# RTS_Hub_V1_2.net
KiCad netlist of a schematic drawn in EAGLE
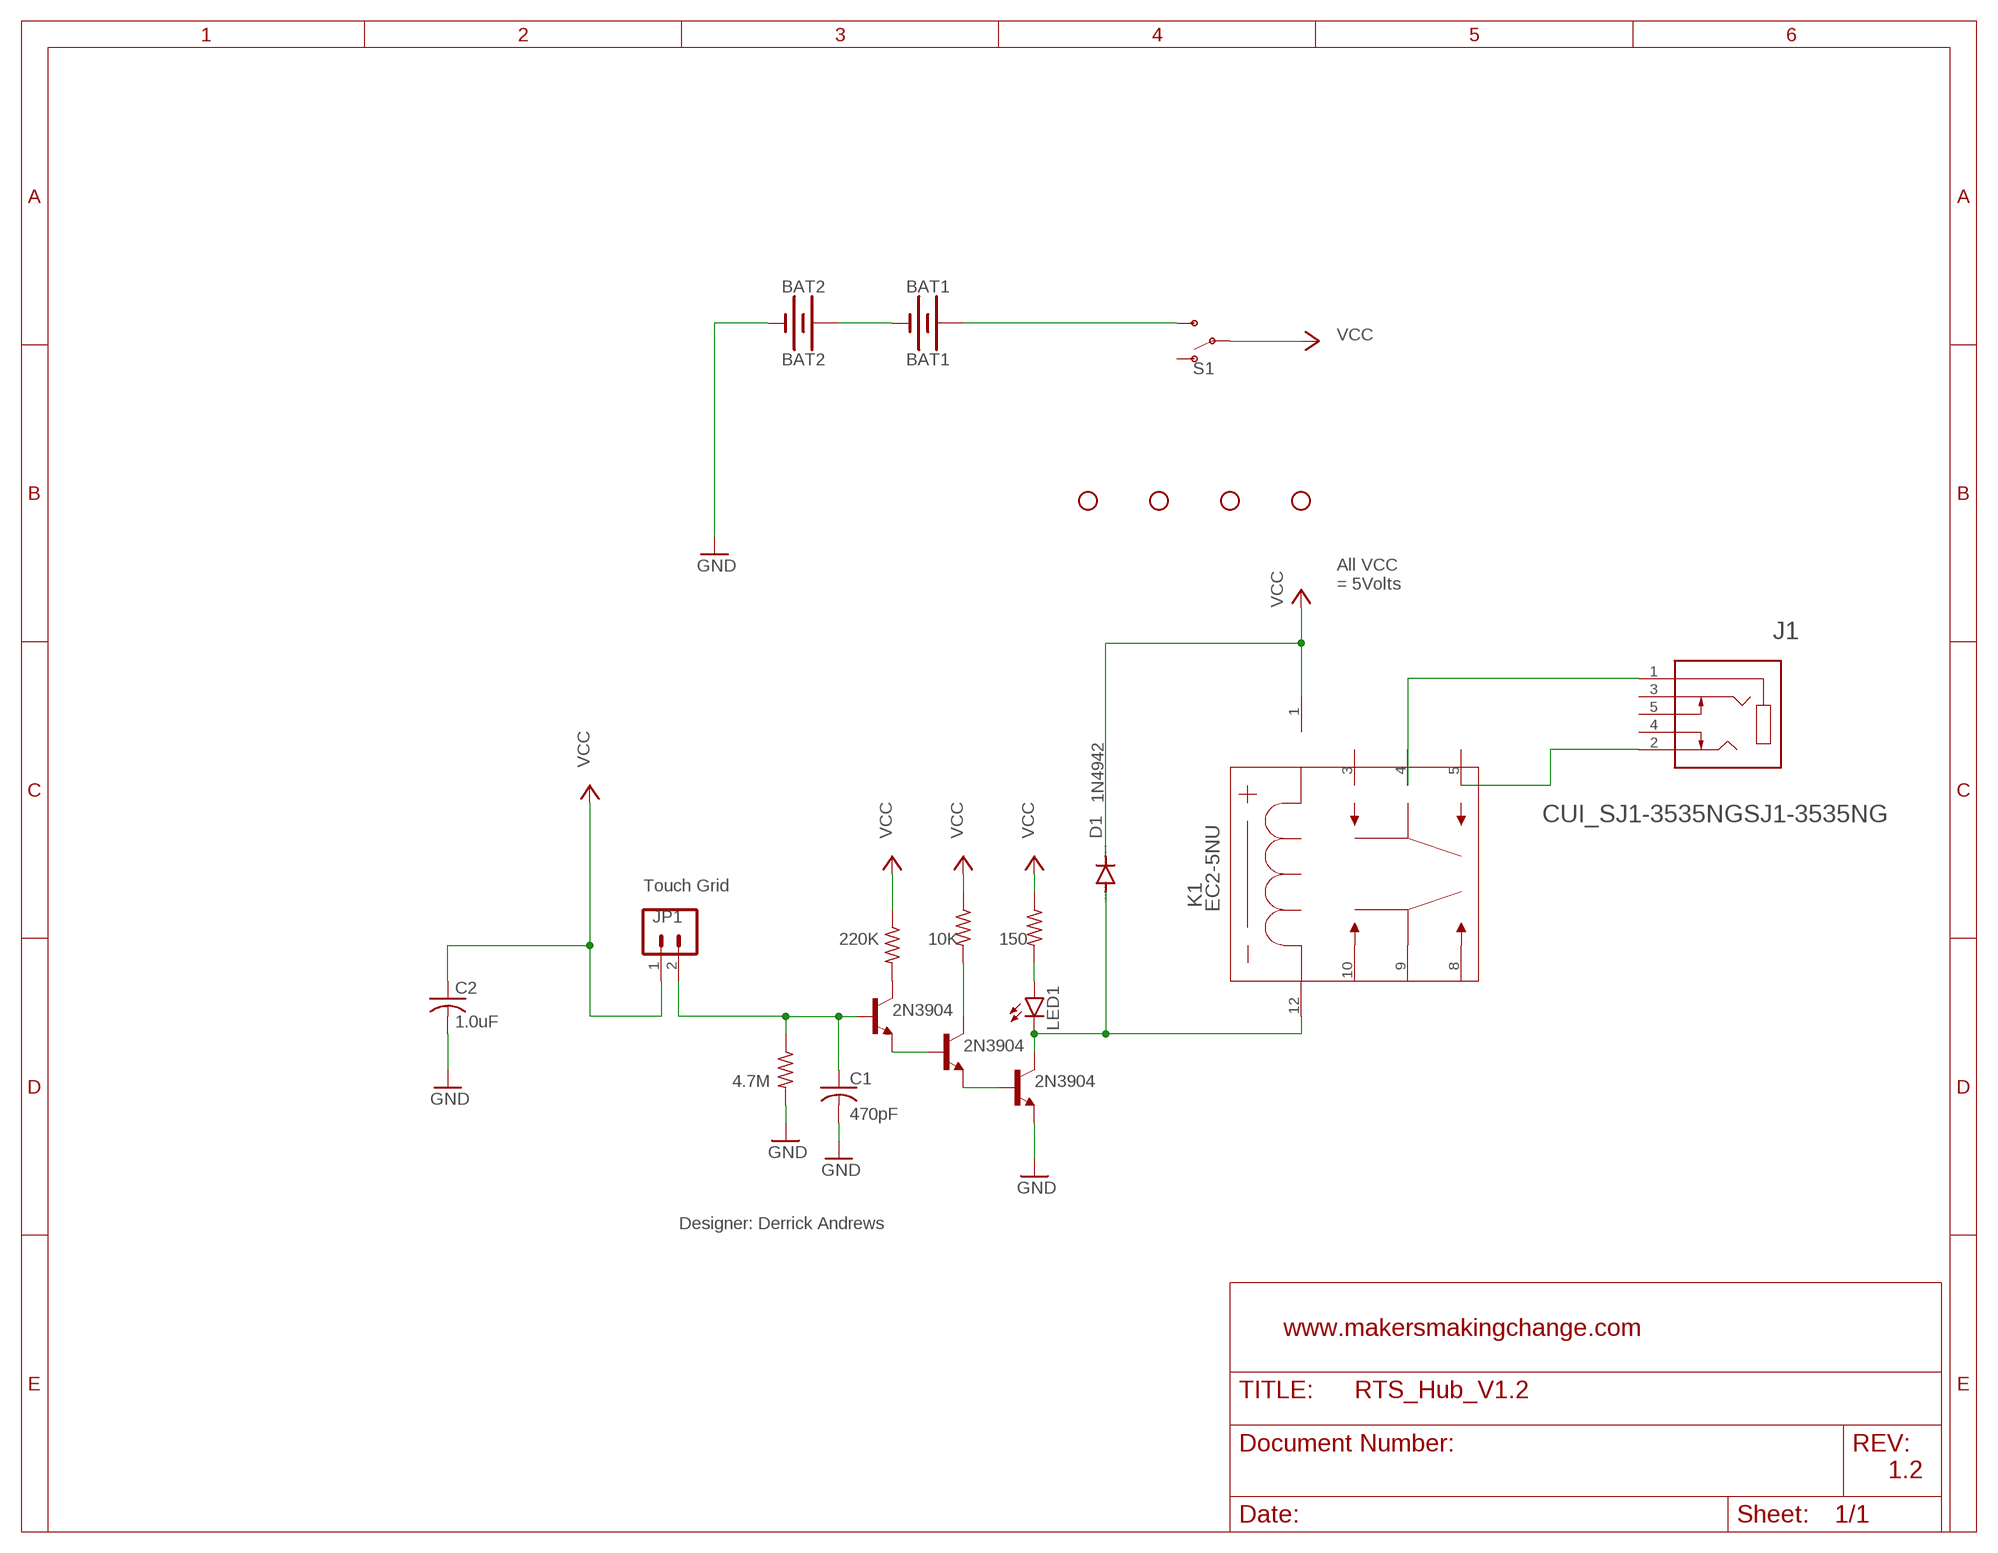
[diagram p0: schematic, sheet 1]

(export (version "E")
  (design (tool "Eeschema 10.0.6"))
  (components
    (comp (ref "BAT1")
      (value "BAT1")
      (footprint "eagle-import:BATTCOM_20MM_PTH")
      (libsource (lib "eagle-import") (part "BATTERY-20MM_PTH"))
    )
    (comp (ref "BAT2")
      (value "BAT2")
      (footprint "eagle-import:BATTCOM_20MM_PTH")
      (libsource (lib "eagle-import") (part "BATTERY-20MM_PTH"))
    )
    (comp (ref "C1")
      (value "470pF")
      (footprint "eagle-import:C025-030X050")
      (libsource (lib "eagle-import") (part "CAPACITOR-US-025"))
    )
    (comp (ref "C2")
      (value "1.0uF")
      (footprint "eagle-import:C050-030X075")
      (libsource (lib "eagle-import") (part "CAPACITOR-US-050"))
    )
    (comp (ref "D1")
      (value "1N4942")
      (footprint "eagle-import:DO41-10")
      (libsource (lib "eagle-import") (part "DIODE-DO41"))
    )
    (comp (ref "H1")
      (value "STAND-OFF-")
      (footprint "eagle-import:STAND-OFF")
      (libsource (lib "eagle-import") (part "STAND-OFF-"))
    )
    (comp (ref "H2")
      (value "STAND-OFF-")
      (footprint "eagle-import:STAND-OFF")
      (libsource (lib "eagle-import") (part "STAND-OFF-"))
    )
    (comp (ref "H3")
      (value "STAND-OFF-")
      (footprint "eagle-import:STAND-OFF")
      (libsource (lib "eagle-import") (part "STAND-OFF-"))
    )
    (comp (ref "H4")
      (value "STAND-OFF-")
      (footprint "eagle-import:STAND-OFF")
      (libsource (lib "eagle-import") (part "STAND-OFF-"))
    )
    (comp (ref "J1")
      (value "CUI_SJ1-3535NGSJ1-3535NG")
      (footprint "eagle-import:CUI_SJ1-3535NG")
      (libsource (lib "eagle-import") (part "CUI_SJ1-3535NGSJ1-3535NG"))
    )
    (comp (ref "JP1")
      (value "HEADER_1X02-1X02")
      (footprint "eagle-import:1X02")
      (libsource (lib "eagle-import") (part "HEADER_1X02-1X02"))
    )
    (comp (ref "K1")
      (value "EC2-5NU")
      (footprint "eagle-import:EC2NU")
      (fields (field (name "MANUFACTURER_PART_NUMBER") "EC25NU"))
      (libsource (lib "eagle-import") (part "EC2-5NU"))
    )
    (comp (ref "LED1")
      (value "LED5MM")
      (footprint "eagle-import:LED_5MM")
      (libsource (lib "eagle-import") (part "LED5MM"))
    )
    (comp (ref "R1")
      (value "10K")
      (footprint "eagle-import:RESISTOR_0207_7")
      (libsource (lib "eagle-import") (part "RESISTOR-US-0207/7"))
    )
    (comp (ref "R2")
      (value "4.7M")
      (footprint "eagle-import:RESISTOR_0207_7")
      (libsource (lib "eagle-import") (part "RESISTOR-US-0207/7"))
    )
    (comp (ref "R3")
      (value "220K")
      (footprint "eagle-import:RESISTOR_0207_7")
      (libsource (lib "eagle-import") (part "RESISTOR-US-0207/7"))
    )
    (comp (ref "R4")
      (value "150")
      (footprint "eagle-import:RESISTOR_0207_7")
      (libsource (lib "eagle-import") (part "RESISTOR-US-0207/7"))
    )
    (comp (ref "S1")
      (value "SWITCH-SPDT-PTH_11.6X4.0MM")
      (footprint "eagle-import:SWITCH_SPDT_PTH_11.6X4.0MM")
      (libsource (lib "eagle-import") (part "SWITCH-SPDT-PTH_11.6X4.0MM"))
    )
    (comp (ref "T1")
      (value "2N3904")
      (footprint "eagle-import:TO92-CBE")
      (libsource (lib "eagle-import") (part "2N3904"))
    )
    (comp (ref "T2")
      (value "2N3904")
      (footprint "eagle-import:TO92-CBE")
      (libsource (lib "eagle-import") (part "2N3904"))
    )
    (comp (ref "T3")
      (value "2N3904")
      (footprint "eagle-import:TO92-CBE")
      (libsource (lib "eagle-import") (part "2N3904"))
    )
  )
  (nets
    (net (code "1") (name "GND") (class "Default")
      (node (ref "BAT2") (pin "-") (pinfunction "-_-") (pintype "power_in"))
      (node (ref "C1") (pin "2") (pinfunction "2_2") (pintype "passive"))
      (node (ref "C2") (pin "2") (pinfunction "2_2") (pintype "passive"))
      (node (ref "R2") (pin "2") (pinfunction "2_2") (pintype "passive"))
      (node (ref "T1") (pin "E") (pinfunction "E_E") (pintype "passive"))
    )
    (net (code "2") (name "Net-(BAT1-Pad-)") (class "Default")
      (node (ref "BAT1") (pin "-") (pinfunction "-_-") (pintype "power_in"))
      (node (ref "BAT2") (pin "+") (pinfunction "+_+") (pintype "power_in"))
    )
    (net (code "3") (name "Net-(C1-Pad1)") (class "Default")
      (node (ref "C1") (pin "1") (pinfunction "1_1") (pintype "passive"))
      (node (ref "JP1") (pin "2") (pinfunction "2_2") (pintype "passive"))
      (node (ref "R2") (pin "1") (pinfunction "1_1") (pintype "passive"))
      (node (ref "T3") (pin "B") (pinfunction "B_B") (pintype "passive"))
    )
    (net (code "4") (name "Net-(K1-3)") (class "Default")
      (node (ref "J1") (pin "1") (pinfunction "1_1") (pintype "passive"))
      (node (ref "K1") (pin "4") (pinfunction "3_4") (pintype "passive"))
    )
    (net (code "5") (name "Net-(K1-4)") (class "Default")
      (node (ref "J1") (pin "2") (pinfunction "2_2") (pintype "passive"))
      (node (ref "K1") (pin "5") (pinfunction "4_5") (pintype "passive"))
    )
    (net (code "6") (name "Net-(K1-8)") (class "Default")
      (node (ref "D1") (pin "A") (pinfunction "A_A") (pintype "passive"))
      (node (ref "K1") (pin "12") (pinfunction "8_12") (pintype "passive"))
      (node (ref "LED1") (pin "K") (pinfunction "C_K") (pintype "passive"))
      (node (ref "T1") (pin "C") (pinfunction "C_C") (pintype "passive"))
    )
    (net (code "7") (name "Net-(LED1-PadA)") (class "Default")
      (node (ref "LED1") (pin "A") (pinfunction "A_A") (pintype "passive"))
      (node (ref "R4") (pin "2") (pinfunction "2_2") (pintype "passive"))
    )
    (net (code "8") (name "Net-(R1-Pad2)") (class "Default")
      (node (ref "R1") (pin "2") (pinfunction "2_2") (pintype "passive"))
      (node (ref "T2") (pin "C") (pinfunction "C_C") (pintype "passive"))
    )
    (net (code "9") (name "Net-(R3-Pad2)") (class "Default")
      (node (ref "R3") (pin "2") (pinfunction "2_2") (pintype "passive"))
      (node (ref "T3") (pin "C") (pinfunction "C_C") (pintype "passive"))
    )
    (net (code "10") (name "Net-(S1-S)") (class "Default")
      (node (ref "BAT1") (pin "+") (pinfunction "+_+") (pintype "power_in"))
      (node (ref "S1") (pin "3") (pinfunction "S_3") (pintype "passive"))
    )
    (net (code "11") (name "Net-(T1-PadB)") (class "Default")
      (node (ref "T1") (pin "B") (pinfunction "B_B") (pintype "passive"))
      (node (ref "T2") (pin "E") (pinfunction "E_E") (pintype "passive"))
    )
    (net (code "12") (name "Net-(T2-PadB)") (class "Default")
      (node (ref "T2") (pin "B") (pinfunction "B_B") (pintype "passive"))
      (node (ref "T3") (pin "E") (pinfunction "E_E") (pintype "passive"))
    )
    (net (code "13") (name "VCC") (class "Default")
      (node (ref "C2") (pin "1") (pinfunction "1_1") (pintype "passive"))
      (node (ref "D1") (pin "C") (pinfunction "C_C") (pintype "passive"))
      (node (ref "JP1") (pin "1") (pinfunction "1_1") (pintype "passive"))
      (node (ref "K1") (pin "1") (pinfunction "1_1") (pintype "passive"))
      (node (ref "R1") (pin "1") (pinfunction "1_1") (pintype "passive"))
      (node (ref "R3") (pin "1") (pinfunction "1_1") (pintype "passive"))
      (node (ref "R4") (pin "1") (pinfunction "1_1") (pintype "passive"))
      (node (ref "S1") (pin "2") (pinfunction "P_2") (pintype "passive"))
    )
    (net (code "14") (name "unconnected-(J1-Pad3)") (class "Default")
      (node (ref "J1") (pin "3") (pinfunction "3_3") (pintype "passive"))
    )
    (net (code "15") (name "unconnected-(J1-Pad4)") (class "Default")
      (node (ref "J1") (pin "4") (pinfunction "4_4") (pintype "passive"))
    )
    (net (code "16") (name "unconnected-(J1-Pad5)") (class "Default")
      (node (ref "J1") (pin "5") (pinfunction "5_5") (pintype "passive"))
    )
    (net (code "17") (name "unconnected-(K1-2-Pad3)") (class "Default")
      (node (ref "K1") (pin "3") (pinfunction "2_3") (pintype "passive"))
    )
    (net (code "18") (name "unconnected-(K1-5-Pad8)") (class "Default")
      (node (ref "K1") (pin "8") (pinfunction "5_8") (pintype "passive"))
    )
    (net (code "19") (name "unconnected-(K1-6-Pad9)") (class "Default")
      (node (ref "K1") (pin "9") (pinfunction "6_9") (pintype "passive"))
    )
    (net (code "20") (name "unconnected-(K1-7-Pad10)") (class "Default")
      (node (ref "K1") (pin "10") (pinfunction "7_10") (pintype "passive"))
    )
    (net (code "21") (name "unconnected-(S1-O-Pad1)") (class "Default")
      (node (ref "S1") (pin "1") (pinfunction "O_1") (pintype "passive"))
    )
  )
)
